# SOM_Console.net
KiCad netlist of a schematic drawn in Altium Designer
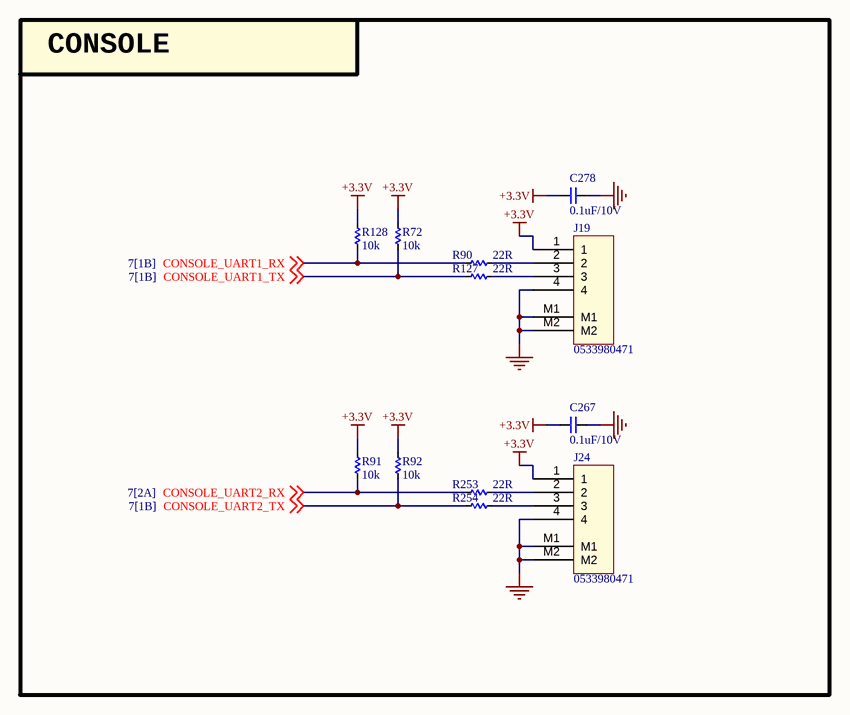
[diagram p0: SOM_Console.SchDoc]

(export (version "E")
  (design (tool "Eeschema 10.0.6"))
  (components
    (comp (ref "C267")
      (value "0.1uF/10V")
      (footprint "CAP_C_1005X60")
      (description "CAP CHIP")
      (libsource (lib "LABLIB") (part "_CAP_C_2"))
    )
    (comp (ref "C278")
      (value "0.1uF/10V")
      (footprint "CAP_C_1005X60")
      (description "CAP CHIP")
      (libsource (lib "LABLIB") (part "_CAP_C_2"))
    )
    (comp (ref "J19")
      (value "0533980471")
      (footprint "MOLEX_0533980471")
      (libsource (lib "LABLIB") (part "Header 4x1_2M"))
    )
    (comp (ref "J24")
      (value "0533980471")
      (footprint "MOLEX_0533980471")
      (libsource (lib "LABLIB") (part "Header 4x1_2M"))
    )
    (comp (ref "R72")
      (value "10k")
      (footprint "RES_C_1005X40")
      (description "RES")
      (libsource (lib "LABLIB") (part "_RES_B_2"))
    )
    (comp (ref "R90")
      (value "22R")
      (footprint "RES_C_1005X40")
      (description "RES")
      (libsource (lib "LABLIB") (part "_RES_B_2"))
    )
    (comp (ref "R91")
      (value "10k")
      (footprint "RES_C_1005X40")
      (description "RES")
      (libsource (lib "LABLIB") (part "_RES_B_2"))
    )
    (comp (ref "R92")
      (value "10k")
      (footprint "RES_C_1005X40")
      (description "RES")
      (libsource (lib "LABLIB") (part "_RES_B_2"))
    )
    (comp (ref "R127")
      (value "22R")
      (footprint "RES_C_1005X40")
      (description "RES")
      (libsource (lib "LABLIB") (part "_RES_B_2"))
    )
    (comp (ref "R128")
      (value "10k")
      (footprint "RES_C_1005X40")
      (description "RES")
      (libsource (lib "LABLIB") (part "_RES_B_2"))
    )
    (comp (ref "R253")
      (value "22R")
      (footprint "RES_C_1005X40")
      (description "RES")
      (libsource (lib "LABLIB") (part "_RES_B_2"))
    )
    (comp (ref "R254")
      (value "22R")
      (footprint "RES_C_1005X40")
      (description "RES")
      (libsource (lib "LABLIB") (part "_RES_B_2"))
    )
  )
  (nets
    (net (code "1") (name "+3.3V") (class "Default")
      (node (ref "C267") (pin "2") (pinfunction "2_2") (pintype "passive"))
      (node (ref "C278") (pin "2") (pinfunction "2_2") (pintype "passive"))
      (node (ref "J19") (pin "1") (pinfunction "1_1") (pintype "passive"))
      (node (ref "J24") (pin "1") (pinfunction "1_1") (pintype "passive"))
      (node (ref "R128") (pin "2") (pinfunction "2_2") (pintype "passive"))
      (node (ref "R72") (pin "2") (pinfunction "2_2") (pintype "passive"))
      (node (ref "R91") (pin "2") (pinfunction "2_2") (pintype "passive"))
      (node (ref "R92") (pin "2") (pinfunction "2_2") (pintype "passive"))
    )
    (net (code "2") (name "CONSOLE_UART1_RX") (class "Default")
      (node (ref "R128") (pin "1") (pinfunction "1_1") (pintype "passive"))
      (node (ref "R90") (pin "2") (pinfunction "2_2") (pintype "passive"))
    )
    (net (code "3") (name "CONSOLE_UART1_TX") (class "Default")
      (node (ref "R127") (pin "2") (pinfunction "2_2") (pintype "passive"))
      (node (ref "R72") (pin "1") (pinfunction "1_1") (pintype "passive"))
    )
    (net (code "4") (name "CONSOLE_UART2_RX") (class "Default")
      (node (ref "R253") (pin "2") (pinfunction "2_2") (pintype "passive"))
      (node (ref "R91") (pin "1") (pinfunction "1_1") (pintype "passive"))
    )
    (net (code "5") (name "CONSOLE_UART2_TX") (class "Default")
      (node (ref "R254") (pin "2") (pinfunction "2_2") (pintype "passive"))
      (node (ref "R92") (pin "1") (pinfunction "1_1") (pintype "passive"))
    )
    (net (code "6") (name "GND") (class "Default")
      (node (ref "C267") (pin "1") (pinfunction "1_1") (pintype "passive"))
      (node (ref "C278") (pin "1") (pinfunction "1_1") (pintype "passive"))
      (node (ref "J19") (pin "4") (pinfunction "4_4") (pintype "passive"))
      (node (ref "J19") (pin "M1") (pinfunction "M1_M1") (pintype "passive"))
      (node (ref "J19") (pin "M2") (pinfunction "M2_M2") (pintype "passive"))
      (node (ref "J24") (pin "4") (pinfunction "4_4") (pintype "passive"))
      (node (ref "J24") (pin "M1") (pinfunction "M1_M1") (pintype "passive"))
      (node (ref "J24") (pin "M2") (pinfunction "M2_M2") (pintype "passive"))
    )
    (net (code "7") (name "Net-(J19-Pad2)") (class "Default")
      (node (ref "J19") (pin "2") (pinfunction "2_2") (pintype "passive"))
      (node (ref "R90") (pin "1") (pinfunction "1_1") (pintype "passive"))
    )
    (net (code "8") (name "Net-(J19-Pad3)") (class "Default")
      (node (ref "J19") (pin "3") (pinfunction "3_3") (pintype "passive"))
      (node (ref "R127") (pin "1") (pinfunction "1_1") (pintype "passive"))
    )
    (net (code "9") (name "Net-(J24-Pad2)") (class "Default")
      (node (ref "J24") (pin "2") (pinfunction "2_2") (pintype "passive"))
      (node (ref "R253") (pin "1") (pinfunction "1_1") (pintype "passive"))
    )
    (net (code "10") (name "Net-(J24-Pad3)") (class "Default")
      (node (ref "J24") (pin "3") (pinfunction "3_3") (pintype "passive"))
      (node (ref "R254") (pin "1") (pinfunction "1_1") (pintype "passive"))
    )
  )
)
